# dc-dc_0_2.net
KiCad netlist of a schematic drawn in EAGLE
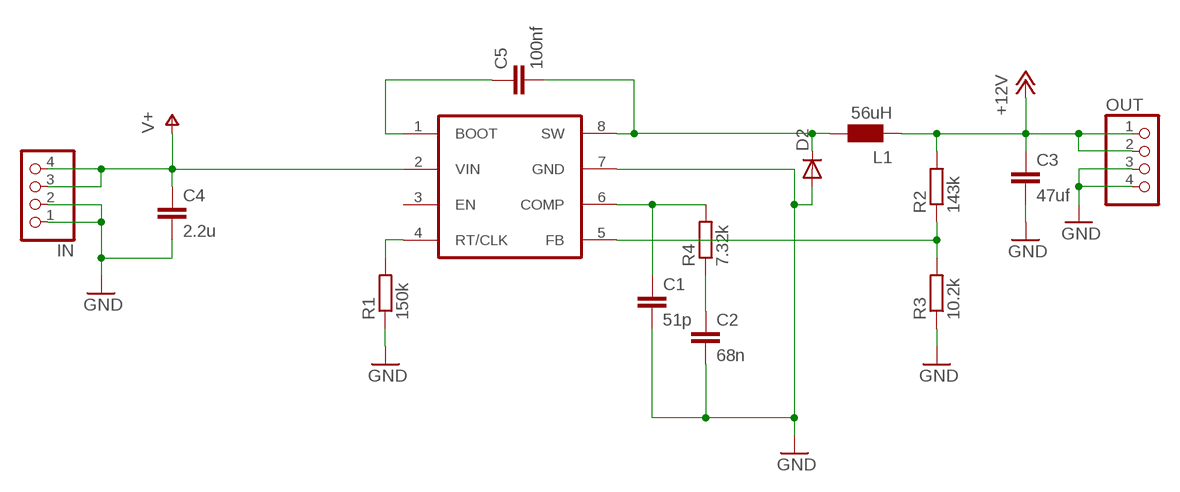
[diagram p0: schematic, sheet 1]

(export (version "E")
  (design (tool "Eeschema 10.0.6"))
  (components
    (comp (ref "C1")
      (value "51p")
      (footprint "eagle-import:C0805")
      (libsource (lib "eagle-import") (part "C-EUC0805"))
    )
    (comp (ref "C2")
      (value "68n")
      (footprint "eagle-import:C1206")
      (libsource (lib "eagle-import") (part "C-EUC1206"))
    )
    (comp (ref "C3")
      (value "47uf")
      (footprint "eagle-import:C1210")
      (libsource (lib "eagle-import") (part "C-EUC1210"))
    )
    (comp (ref "C4")
      (value "2.2u")
      (footprint "eagle-import:C1210")
      (libsource (lib "eagle-import") (part "C-EUC1210"))
    )
    (comp (ref "C5")
      (value "100nf")
      (footprint "eagle-import:C0805")
      (libsource (lib "eagle-import") (part "C-EUC0805"))
    )
    (comp (ref "D2")
      (value "DIODE-DO-214AC")
      (footprint "eagle-import:DO-214AC")
      (libsource (lib "eagle-import") (part "DIODE-DO-214AC"))
    )
    (comp (ref "IN")
      (value "PINHD-1X4")
      (footprint "eagle-import:1X04")
      (libsource (lib "eagle-import") (part "PINHD-1X4"))
    )
    (comp (ref "L1")
      (value "56uH")
      (footprint "eagle-import:WE-PD_L_XL_XXL")
      (libsource (lib "eagle-import") (part "WE-PD_L/XL/XXL"))
    )
    (comp (ref "OUT")
      (value "PINHD-1X4")
      (footprint "eagle-import:1X04")
      (libsource (lib "eagle-import") (part "PINHD-1X4"))
    )
    (comp (ref "R1")
      (value "150k")
      (footprint "eagle-import:R0805")
      (libsource (lib "eagle-import") (part "R-EU_R0805"))
    )
    (comp (ref "R2")
      (value "143k")
      (footprint "eagle-import:R0805")
      (libsource (lib "eagle-import") (part "R-EU_R0805"))
    )
    (comp (ref "R3")
      (value "10.2k")
      (footprint "eagle-import:R0805")
      (libsource (lib "eagle-import") (part "R-EU_R0805"))
    )
    (comp (ref "R4")
      (value "7.32k")
      (footprint "eagle-import:R0805")
      (libsource (lib "eagle-import") (part "R-EU_R0805"))
    )
    (comp (ref "U1")
      (value "TPS54560")
      (footprint "eagle-import:SO08-POWERPAD")
      (libsource (lib "eagle-import") (part "TPS54560"))
    )
  )
  (nets
    (net (code "1") (name "+12V") (class "Default")
      (node (ref "C3") (pin "1") (pinfunction "1_1") (pintype "passive"))
      (node (ref "L1") (pin "2") (pinfunction "1_2") (pintype "passive"))
      (node (ref "OUT") (pin "1") (pinfunction "1_1") (pintype "passive"))
      (node (ref "OUT") (pin "2") (pinfunction "2_2") (pintype "passive"))
      (node (ref "R2") (pin "2") (pinfunction "2_2") (pintype "passive"))
    )
    (net (code "2") (name "GND") (class "Default")
      (node (ref "C1") (pin "2") (pinfunction "2_2") (pintype "passive"))
      (node (ref "C2") (pin "2") (pinfunction "2_2") (pintype "passive"))
      (node (ref "C3") (pin "2") (pinfunction "2_2") (pintype "passive"))
      (node (ref "C4") (pin "2") (pinfunction "2_2") (pintype "passive"))
      (node (ref "D2") (pin "A") (pinfunction "A_A") (pintype "passive"))
      (node (ref "IN") (pin "1") (pinfunction "1_1") (pintype "passive"))
      (node (ref "IN") (pin "2") (pinfunction "2_2") (pintype "passive"))
      (node (ref "OUT") (pin "3") (pinfunction "3_3") (pintype "passive"))
      (node (ref "OUT") (pin "4") (pinfunction "4_4") (pintype "passive"))
      (node (ref "R1") (pin "1") (pinfunction "1_1") (pintype "passive"))
      (node (ref "R3") (pin "1") (pinfunction "1_1") (pintype "passive"))
      (node (ref "U1") (pin "7") (pinfunction "GND_7") (pintype "input"))
    )
    (net (code "3") (name "Net-(C2-Pad1)") (class "Default")
      (node (ref "C2") (pin "1") (pinfunction "1_1") (pintype "passive"))
      (node (ref "R4") (pin "1") (pinfunction "1_1") (pintype "passive"))
    )
    (net (code "4") (name "Net-(L1-2)") (class "Default")
      (node (ref "C5") (pin "2") (pinfunction "2_2") (pintype "passive"))
      (node (ref "D2") (pin "C") (pinfunction "C_C") (pintype "passive"))
      (node (ref "L1") (pin "1") (pinfunction "2_1") (pintype "passive"))
      (node (ref "U1") (pin "8") (pinfunction "SW_8") (pintype "output"))
    )
    (net (code "5") (name "Net-(U1-BOOT)") (class "Default")
      (node (ref "C5") (pin "1") (pinfunction "1_1") (pintype "passive"))
      (node (ref "U1") (pin "1") (pinfunction "BOOT_1") (pintype "input"))
    )
    (net (code "6") (name "Net-(U1-COMP)") (class "Default")
      (node (ref "C1") (pin "1") (pinfunction "1_1") (pintype "passive"))
      (node (ref "R4") (pin "2") (pinfunction "2_2") (pintype "passive"))
      (node (ref "U1") (pin "6") (pinfunction "COMP_6") (pintype "output"))
    )
    (net (code "7") (name "Net-(U1-FB)") (class "Default")
      (node (ref "R2") (pin "1") (pinfunction "1_1") (pintype "passive"))
      (node (ref "R3") (pin "2") (pinfunction "2_2") (pintype "passive"))
      (node (ref "U1") (pin "5") (pinfunction "FB_5") (pintype "passive"))
    )
    (net (code "8") (name "Net-(U1-RT{slash}CLK)") (class "Default")
      (node (ref "R1") (pin "2") (pinfunction "2_2") (pintype "passive"))
      (node (ref "U1") (pin "4") (pinfunction "RT/CLK_4") (pintype "input"))
    )
    (net (code "9") (name "V+") (class "Default")
      (node (ref "C4") (pin "1") (pinfunction "1_1") (pintype "passive"))
      (node (ref "IN") (pin "3") (pinfunction "3_3") (pintype "passive"))
      (node (ref "IN") (pin "4") (pinfunction "4_4") (pintype "passive"))
      (node (ref "U1") (pin "2") (pinfunction "VIN_2") (pintype "input"))
    )
    (net (code "10") (name "unconnected-(U1-EN-Pad3)") (class "Default")
      (node (ref "U1") (pin "3") (pinfunction "EN_3") (pintype "input"))
    )
  )
)
